# Half_Bridge.net
KiCad netlist of a schematic drawn in Altium Designer
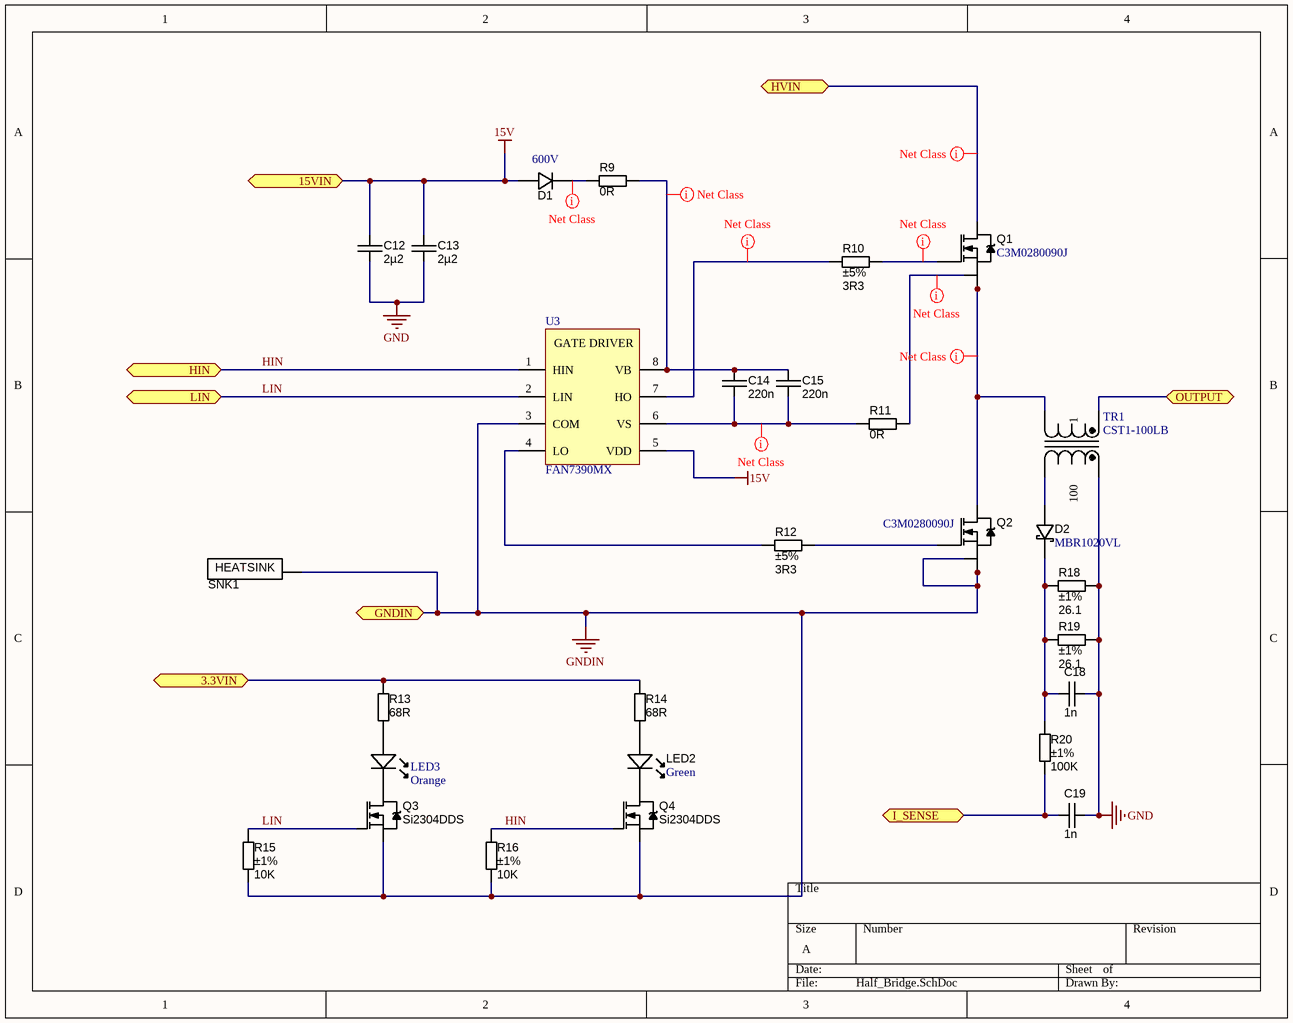
[diagram p0: Half_Bridge.SchDoc]

(export (version "E")
  (design (tool "Eeschema 10.0.6"))
  (components
    (comp (ref "C12")
      (value "2µ2")
      (footprint "CAPC3216X180N")
      (description "Capacitor SMD Cer 2.2uF 10% 50V X7R 1206")
      (fields (field (name "TOLERANCE") "±10%") (field (name "Comment") "approved sub OK"))
      (libsource (lib "PBL - Capacitors") (part "CAPC_2u2_50V_1206"))
    )
    (comp (ref "C13")
      (value "2µ2")
      (footprint "CAPC3216X180N")
      (description "Capacitor SMD Cer 2.2uF 10% 50V X7R 1206")
      (fields (field (name "TOLERANCE") "±10%") (field (name "Comment") "approved sub OK"))
      (libsource (lib "PBL - Capacitors") (part "CAPC_2u2_50V_1206"))
    )
    (comp (ref "C14")
      (value "220n")
      (footprint "CAPC1632X07N")
      (description "Capacitor SMD Cer 220nF 10% 25V X7R 0612")
      (fields (field (name "MANUFACTURER") "AVX Corporation") (field (name "TOLERANCE") "±20%"))
      (libsource (lib "PBL - Capacitors") (part "CAPC_220n_0612_X7R_25V_10%"))
    )
    (comp (ref "C15")
      (value "220n")
      (footprint "CAPC1632X07N")
      (description "Capacitor SMD Cer 220nF 10% 25V X7R 0612")
      (fields (field (name "MANUFACTURER") "AVX Corporation") (field (name "TOLERANCE") "±20%"))
      (libsource (lib "PBL - Capacitors") (part "CAPC_220n_0612_X7R_25V_10%"))
    )
    (comp (ref "C18")
      (value "1n")
      (footprint "CAPC1608X90N")
      (description "Capacitor SMD Cer 1nF 10% 100V X7R 0603")
      (fields (field (name "TOLERANCE") "±10%") (field (name "Comment") "approved sub OK"))
      (libsource (lib "PBL - Capacitors") (part "CAPC_1n_0603_X7R_100V_10%"))
    )
    (comp (ref "C19")
      (value "1n")
      (footprint "CAPC1608X90N")
      (description "Capacitor SMD Cer 1nF 10% 100V X7R 0603")
      (fields (field (name "TOLERANCE") "±10%") (field (name "Comment") "approved sub OK"))
      (libsource (lib "PBL - Capacitors") (part "CAPC_1n_0603_X7R_100V_10%"))
    )
    (comp (ref "D1")
      (value "ER2J-LTP")
      (footprint "DO-214AA")
      (description "Diode Standard 600V 2A Surface Mount DO-214AA (SMB)")
      (fields
        (field (name "MANUFACTURER") "Micro Commercial Co")
        (field (name "VOLTAGE - DC REVERSE (VR) (MAX)") "600V")
      )
      (libsource (lib "PBL - Diodes") (part "DIODE_600V_2A_ER2J-LTP"))
    )
    (comp (ref "D2")
      (value "B320A-13-F")
      (footprint "SOD123F")
      (description "Diode Schottky 20V 1A Surface Mount SOD-123F")
      (fields
        (field (name "MANUFACTURER") "Fairchild/ON Semiconductor")
        (field (name "MANUFACTURER PART NUMBER") "MBR1020VL")
      )
      (libsource (lib "PBL - Diodes") (part "DIODE_SCHOTTKY_20V_1A_MBR1020VL"))
    )
    (comp (ref "LED2")
      (value "APT1608CGCK")
      (footprint "LED-0603-GREEN")
      (description "Green 570nm LED Indication - Discrete 2.1V 0603 (1608 Metric)")
      (fields (field (name "MANUFACTURER") "Kingbright") (field (name "COLOR") "Green"))
      (libsource (lib "PBL - Light Sources") (part "LED_SMD_Green_0603_50mcd"))
    )
    (comp (ref "LED3")
      (value "LO L296-Q2S1-24-Z")
      (footprint "LED-0603-AMBER")
      (description "LED ORANGE DIFFUSED 0603 SMD")
      (fields (field (name "COLOR") "Orange") (field (name "MANUFACTURER") "OSRAM Opto Semiconductors Inc."))
      (libsource (lib "PBL - Light Sources") (part "LED_0603_Orange"))
    )
    (comp (ref "Q1")
      (value "C3M0065090D")
      (footprint "DPAK127P1618X457-8N")
      (description "N-Channel 36A (Tc) 125W (Tc) Through Hole TO-247-3")
      (fields
        (field (name "MANUFACTURER") "Cree/Wolfspeed")
        (field (name "MANUFACTURER PART NUMBER") "C3M0280090J")
      )
      (libsource (lib "PBL - Transistors") (part "SiC_N-CHAN_900V_11A_C3M0280090J"))
    )
    (comp (ref "Q2")
      (value "C3M0065090D")
      (footprint "DPAK127P1618X457-8N")
      (description "N-Channel 36A (Tc) 125W (Tc) Through Hole TO-247-3")
      (fields
        (field (name "MANUFACTURER") "Cree/Wolfspeed")
        (field (name "MANUFACTURER PART NUMBER") "C3M0280090J")
      )
      (libsource (lib "PBL - Transistors") (part "SiC_N-CHAN_900V_11A_C3M0280090J"))
    )
    (comp (ref "Q3")
      (value "Si2304DDS")
      (footprint "SOT23-3")
      (description "MOSFET SMD N-CH 30V 3.6A 1.7W SOT23-3")
      (libsource (lib "PBL - Transistors") (part "MOSFET_Si2304DDS"))
    )
    (comp (ref "Q4")
      (value "Si2304DDS")
      (footprint "SOT23-3")
      (description "MOSFET SMD N-CH 30V 3.6A 1.7W SOT23-3")
      (libsource (lib "PBL - Transistors") (part "MOSFET_Si2304DDS"))
    )
    (comp (ref "R9")
      (value "0R")
      (footprint "RESC2012X70N")
      (description "Resistor SMD chip 0.0 Ohm 0.125W 0805")
      (fields (field (name "Comment") "Jumper"))
      (libsource (lib "PBL - Resistors") (part "RES_0R_0805"))
    )
    (comp (ref "R10")
      (value "3R3")
      (footprint "RESC2012X70N")
      (description "Resistor SMD chip 3.3 Ohm 0.5W 0805")
      (fields
        (field (name "MANUFACTURER") "Panasonic Electronic Components")
        (field (name "MANUFACTURER PART NUMBER") "ERJ-6DQJ3R0V")
        (field (name "TOLERANCE") "±5%")
      )
      (libsource (lib "PBL - Resistors") (part "RES_3R3_0805_5%"))
    )
    (comp (ref "R11")
      (value "0R")
      (footprint "RESC2012X70N")
      (description "Resistor SMD chip 0.0 Ohm 0.125W 0805")
      (fields (field (name "Comment") "Jumper"))
      (libsource (lib "PBL - Resistors") (part "RES_0R_0805"))
    )
    (comp (ref "R12")
      (value "3R3")
      (footprint "RESC2012X70N")
      (description "Resistor SMD chip 3.3 Ohm 0.5W 0805")
      (fields
        (field (name "MANUFACTURER") "Panasonic Electronic Components")
        (field (name "MANUFACTURER PART NUMBER") "ERJ-6DQJ3R0V")
        (field (name "TOLERANCE") "±5%")
      )
      (libsource (lib "PBL - Resistors") (part "RES_3R3_0805_5%"))
    )
    (comp (ref "R13")
      (value "68R")
      (footprint "RESC1608X55N")
      (description "Resistor SMD chip 68 Ohm 0.1W 5% 0603")
      (fields (field (name "TOLERANCE") "±5%") (field (name "Comment") "Thick Film"))
      (libsource (lib "PBL - Resistors") (part "RES_68R_0603_5%"))
    )
    (comp (ref "R14")
      (value "68R")
      (footprint "RESC1608X55N")
      (description "Resistor SMD chip 68 Ohm 0.1W 5% 0603")
      (fields (field (name "TOLERANCE") "±5%") (field (name "Comment") "Thick Film"))
      (libsource (lib "PBL - Resistors") (part "RES_68R_0603_5%"))
    )
    (comp (ref "R15")
      (value "10K")
      (footprint "RESC1005X40N")
      (description "Resistor SMD chip 10k Ohm 0.063W 1% 0402")
      (fields (field (name "TOLERANCE") "±1%") (field (name "Comment") "Thick Film"))
      (libsource (lib "PBL - Resistors") (part "RES_10K_0402_1%"))
    )
    (comp (ref "R16")
      (value "10K")
      (footprint "RESC1005X40N")
      (description "Resistor SMD chip 10k Ohm 0.063W 1% 0402")
      (fields (field (name "TOLERANCE") "±1%") (field (name "Comment") "Thick Film"))
      (libsource (lib "PBL - Resistors") (part "RES_10K_0402_1%"))
    )
    (comp (ref "R18")
      (value "26.1")
      (footprint "RESC2012X70N")
      (description "Resistor SMD chip 26.1k Ohm 0.125W 1% 0805")
      (fields
        (field (name "MANUFACTURER") "Panasonic Electronic Components")
        (field (name "TOLERANCE") "±1%")
        (field (name "MANUFACTURER PART NUMBER") "ERJ-6ENF26R1V")
      )
      (libsource (lib "PBL - Resistors") (part "RES_26R1_0805_1%"))
    )
    (comp (ref "R19")
      (value "26.1")
      (footprint "RESC2012X70N")
      (description "Resistor SMD chip 26.1k Ohm 0.125W 1% 0805")
      (fields
        (field (name "MANUFACTURER") "Panasonic Electronic Components")
        (field (name "TOLERANCE") "±1%")
        (field (name "MANUFACTURER PART NUMBER") "ERJ-6ENF26R1V")
      )
      (libsource (lib "PBL - Resistors") (part "RES_26R1_0805_1%"))
    )
    (comp (ref "R20")
      (value "100K")
      (footprint "RESC1608X55N")
      (description "Resistor SMD chip 100k Ohm 0.1W 1% 0603")
      (fields (field (name "TOLERANCE") "±1%") (field (name "Comment") "Thick Film"))
      (libsource (lib "PBL - Resistors") (part "RES_100K_0603_1%"))
    )
    (comp (ref "SNK1")
      (value "ATS-CPX025025010-137-C2-R0")
      (footprint "HeatSink ATS-CPX025025010-165-C2-R0")
      (description "Heat Sink Assorted (BGA, LGA, CPU, ASIC...) Aluminum Top Mount")
      (fields (field (name "MANUFACTURER") "Advanced Thermal Solutions Inc."))
      (libsource (lib "PBL - Mechanical") (part "HEATSINK_25mmx25mm_ATS-CPX025025010-137-C2-R0"))
    )
    (comp (ref "TR1")
      (value "CST1-100LB")
      (footprint "CST1")
      (description "Sufrace Mount Current Transformer 100:1 Ratio 20A")
      (libsource (lib "PBL - Transformers") (part "CURRENT_100{colon}1_20A_CST1-100LB"))
    )
    (comp (ref "U3")
      (value "FAN7390MX")
      (footprint "SOIC127P600X175-8AN")
      (description "Half-Bridge Gate Driver IC Non-Inverting 8-SOP")
      (fields
        (field (name "MANUFACTURER") "Fairchild/ON Semiconductor")
        (field (name "MANUFACTURER PART NUMBER") "FAN7390MX")
      )
      (libsource (lib "PBL - Integrated Circuits") (part "GATE_DRV_2_600V_4.5A"))
    )
  )
  (nets
    (net (code "1") (name "/3.3VIN") (class "Default")
      (node (ref "R13") (pin "1") (pinfunction "1_1") (pintype "passive"))
      (node (ref "R14") (pin "1") (pinfunction "1_1") (pintype "passive"))
    )
    (net (code "2") (name "/HIN") (class "Default")
      (node (ref "Q4") (pin "1") (pinfunction "G_1") (pintype "passive"))
      (node (ref "R16") (pin "1") (pinfunction "1_1") (pintype "passive"))
      (node (ref "U3") (pin "1") (pinfunction "HIN_1") (pintype "passive"))
    )
    (net (code "3") (name "/HVIN") (class "Default")
      (node (ref "Q1") (pin "8") (pinfunction "D_8") (pintype "passive"))
    )
    (net (code "4") (name "/I_SENSE") (class "Default")
      (node (ref "C19") (pin "1") (pintype "passive"))
      (node (ref "R20") (pin "1") (pinfunction "1_1") (pintype "passive"))
    )
    (net (code "5") (name "/LIN") (class "Default")
      (node (ref "Q3") (pin "1") (pinfunction "G_1") (pintype "passive"))
      (node (ref "R15") (pin "1") (pinfunction "1_1") (pintype "passive"))
      (node (ref "U3") (pin "2") (pinfunction "LIN_2") (pintype "passive"))
    )
    (net (code "6") (name "/OUTPUT") (class "Default")
      (node (ref "TR1") (pin "8") (pinfunction "8_8") (pintype "passive"))
    )
    (net (code "7") (name "15V") (class "Default")
      (node (ref "C12") (pin "1") (pintype "passive"))
      (node (ref "C13") (pin "1") (pintype "passive"))
      (node (ref "D1") (pin "A") (pinfunction "A_A") (pintype "passive"))
      (node (ref "U3") (pin "5") (pinfunction "VDD_5") (pintype "passive"))
    )
    (net (code "8") (name "GND") (class "Default")
      (node (ref "C12") (pin "2") (pintype "passive"))
      (node (ref "C13") (pin "2") (pintype "passive"))
      (node (ref "C18") (pin "2") (pintype "passive"))
      (node (ref "C19") (pin "2") (pintype "passive"))
      (node (ref "R18") (pin "2") (pinfunction "2_2") (pintype "passive"))
      (node (ref "R19") (pin "2") (pinfunction "2_2") (pintype "passive"))
      (node (ref "TR1") (pin "6") (pinfunction "6_6") (pintype "passive"))
    )
    (net (code "9") (name "GNDIN") (class "Default")
      (node (ref "Q2") (pin "2") (pinfunction "2_2") (pintype "passive"))
      (node (ref "Q2") (pin "3") (pinfunction "S_3") (pintype "passive"))
      (node (ref "Q2") (pin "4") (pinfunction "4_4") (pintype "passive"))
      (node (ref "Q2") (pin "5") (pinfunction "5_5") (pintype "passive"))
      (node (ref "Q2") (pin "6") (pinfunction "6_6") (pintype "passive"))
      (node (ref "Q2") (pin "7") (pinfunction "7_7") (pintype "passive"))
      (node (ref "Q3") (pin "2") (pinfunction "S_2") (pintype "passive"))
      (node (ref "Q4") (pin "2") (pinfunction "S_2") (pintype "passive"))
      (node (ref "R15") (pin "2") (pinfunction "2_2") (pintype "passive"))
      (node (ref "R16") (pin "2") (pinfunction "2_2") (pintype "passive"))
      (node (ref "SNK1") (pin "1") (pinfunction "GND_1") (pintype "passive"))
      (node (ref "U3") (pin "3") (pinfunction "COM_3") (pintype "passive"))
    )
    (net (code "10") (name "Net-(C18-Pad1)") (class "Default")
      (node (ref "C18") (pin "1") (pintype "passive"))
      (node (ref "D2") (pin "K") (pinfunction "K_K") (pintype "passive"))
      (node (ref "R18") (pin "1") (pinfunction "1_1") (pintype "passive"))
      (node (ref "R19") (pin "1") (pinfunction "1_1") (pintype "passive"))
      (node (ref "R20") (pin "2") (pinfunction "2_2") (pintype "passive"))
    )
    (net (code "11") (name "Net-(D1-PadK)") (class "Default")
      (node (ref "D1") (pin "K") (pinfunction "K_K") (pintype "passive"))
      (node (ref "R9") (pin "1") (pinfunction "1_1") (pintype "passive"))
    )
    (net (code "12") (name "Net-(D2-PadA)") (class "Default")
      (node (ref "D2") (pin "A") (pinfunction "A_A") (pintype "passive"))
      (node (ref "TR1") (pin "4") (pinfunction "4_4") (pintype "passive"))
    )
    (net (code "13") (name "Net-(LED2-PadA)") (class "Default")
      (node (ref "LED2") (pin "A") (pinfunction "A_A") (pintype "passive"))
      (node (ref "R14") (pin "2") (pinfunction "2_2") (pintype "passive"))
    )
    (net (code "14") (name "Net-(LED3-PadA)") (class "Default")
      (node (ref "LED3") (pin "A") (pinfunction "A_A") (pintype "passive"))
      (node (ref "R13") (pin "2") (pinfunction "2_2") (pintype "passive"))
    )
    (net (code "15") (name "Net-(Q1-G)") (class "Default")
      (node (ref "Q1") (pin "1") (pinfunction "G_1") (pintype "passive"))
      (node (ref "R10") (pin "2") (pinfunction "2_2") (pintype "passive"))
    )
    (net (code "16") (name "Net-(Q1-Pad2)") (class "Default")
      (node (ref "Q1") (pin "2") (pinfunction "2_2") (pintype "passive"))
      (node (ref "R11") (pin "2") (pinfunction "2_2") (pintype "passive"))
    )
    (net (code "17") (name "Net-(Q1-S)") (class "Default")
      (node (ref "Q1") (pin "3") (pinfunction "S_3") (pintype "passive"))
      (node (ref "Q1") (pin "4") (pinfunction "4_4") (pintype "passive"))
      (node (ref "Q1") (pin "5") (pinfunction "5_5") (pintype "passive"))
      (node (ref "Q1") (pin "6") (pinfunction "6_6") (pintype "passive"))
      (node (ref "Q1") (pin "7") (pinfunction "7_7") (pintype "passive"))
      (node (ref "Q2") (pin "8") (pinfunction "D_8") (pintype "passive"))
      (node (ref "TR1") (pin "7") (pinfunction "7_7") (pintype "passive"))
    )
    (net (code "18") (name "Net-(Q2-G)") (class "Default")
      (node (ref "Q2") (pin "1") (pinfunction "G_1") (pintype "passive"))
      (node (ref "R12") (pin "2") (pinfunction "2_2") (pintype "passive"))
    )
    (net (code "19") (name "Net-(Q3-D)") (class "Default")
      (node (ref "LED3") (pin "K") (pinfunction "K_K") (pintype "passive"))
      (node (ref "Q3") (pin "3") (pinfunction "D_3") (pintype "passive"))
    )
    (net (code "20") (name "Net-(Q4-D)") (class "Default")
      (node (ref "LED2") (pin "K") (pinfunction "K_K") (pintype "passive"))
      (node (ref "Q4") (pin "3") (pinfunction "D_3") (pintype "passive"))
    )
    (net (code "21") (name "Net-(U3-HO)") (class "Default")
      (node (ref "R10") (pin "1") (pinfunction "1_1") (pintype "passive"))
      (node (ref "U3") (pin "7") (pinfunction "HO_7") (pintype "passive"))
    )
    (net (code "22") (name "Net-(U3-LO)") (class "Default")
      (node (ref "R12") (pin "1") (pinfunction "1_1") (pintype "passive"))
      (node (ref "U3") (pin "4") (pinfunction "LO_4") (pintype "passive"))
    )
    (net (code "23") (name "Net-(U3-VB)") (class "Default")
      (node (ref "C14") (pin "1") (pintype "passive"))
      (node (ref "C15") (pin "1") (pintype "passive"))
      (node (ref "R9") (pin "2") (pinfunction "2_2") (pintype "passive"))
      (node (ref "U3") (pin "8") (pinfunction "VB_8") (pintype "passive"))
    )
    (net (code "24") (name "Net-(U3-VS)") (class "Default")
      (node (ref "C14") (pin "2") (pintype "passive"))
      (node (ref "C15") (pin "2") (pintype "passive"))
      (node (ref "R11") (pin "1") (pinfunction "1_1") (pintype "passive"))
      (node (ref "U3") (pin "6") (pinfunction "VS_6") (pintype "passive"))
    )
  )
)
